# munia-ngc.net
KiCad netlist of a schematic drawn in EAGLE
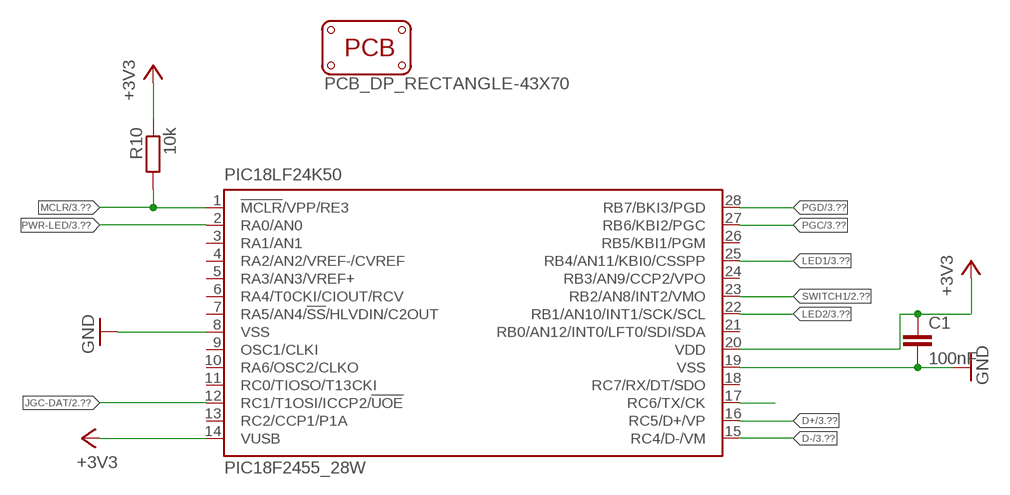
[diagram p0: schematic, sheet 1]
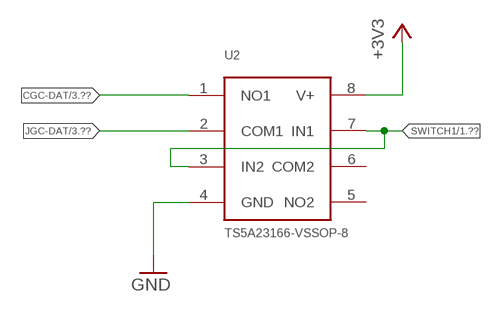
[diagram p1: schematic, sheet 2]
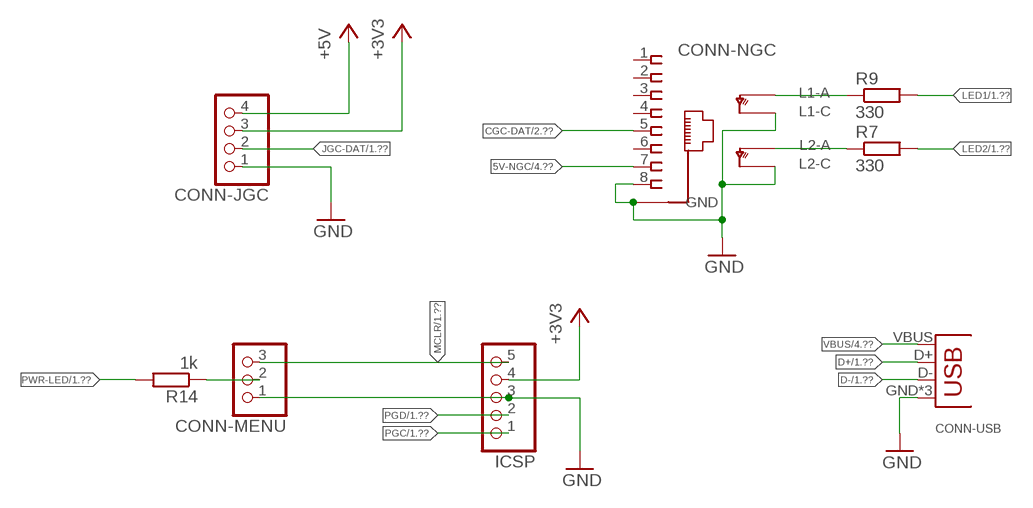
[diagram p2: schematic, sheet 3]
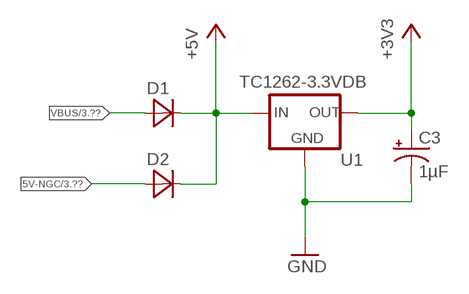
[diagram p3: schematic, sheet 4]

(export (version "E")
  (design (tool "Eeschema 10.0.6"))
  (components
    (comp (ref "C1")
      (value "100nF")
      (footprint "eagle-import:C0603")
      (libsource (lib "eagle-import") (part "C-EUC0603"))
    )
    (comp (ref "PCB1")
      (value "PCB_DP_RECTANGLE-43X70")
      (footprint "eagle-import:DP7043_V1")
      (libsource (lib "eagle-import") (part "PCB_DP_RECTANGLE-43X70"))
    )
    (comp (ref "PIC18LF24K50")
      (value "PIC18F2455_28W")
      (footprint "eagle-import:SO28W")
      (fields (field (name "MF") "MICROCHIP") (field (name "MPN") "PIC18F2455-I/SO"))
      (libsource (lib "eagle-import") (part "PIC18F2_28W455"))
    )
    (comp (ref "R10")
      (value "10k")
      (footprint "eagle-import:R0603")
      (libsource (lib "eagle-import") (part "R-EU_R0603"))
    )
    (comp (ref "C3")
      (value "1µF")
      (footprint "eagle-import:EIA3216")
      (libsource (lib "eagle-import") (part "TANT-CAP1206"))
    )
    (comp (ref "D1")
      (value "MBR120VLSFT1G")
      (footprint "eagle-import:SOD123")
      (libsource (lib "eagle-import") (part "MBR120VLSFT1G"))
    )
    (comp (ref "D2")
      (value "MBR120VLSFT1G")
      (footprint "eagle-import:SOD123")
      (libsource (lib "eagle-import") (part "MBR120VLSFT1G"))
    )
    (comp (ref "U1")
      (value "TC1262-3.3VDB")
      (footprint "eagle-import:SOT230P700X180-4N")
      (libsource (lib "eagle-import") (part "TC1262-3.3VDB"))
    )
    (comp (ref "U2")
      (value "TS5A23166-VSSOP-8")
      (footprint "eagle-import:SOT765")
      (libsource (lib "eagle-import") (part "TS5A23166-VSSOP-8"))
    )
    (comp (ref "CONN-JGC")
      (value "PINHD-1X4")
      (footprint "eagle-import:1X04")
      (libsource (lib "eagle-import") (part "PINHD-1X4"))
    )
    (comp (ref "CONN-MENU")
      (value "PINHD-1X3")
      (footprint "eagle-import:1X03")
      (libsource (lib "eagle-import") (part "PINHD-1X3"))
    )
    (comp (ref "CONN-NGC")
      (value "RJ45-NIELS")
      (footprint "eagle-import:RJ45-NIELS")
      (libsource (lib "eagle-import") (part "RJ45-NIELS"))
    )
    (comp (ref "CONN-USB")
      (value "USB-B-NIELS")
      (footprint "eagle-import:USB-B-H")
      (libsource (lib "eagle-import") (part "USB-B-NIELS"))
    )
    (comp (ref "ICSP")
      (value "PINHD-1X5")
      (footprint "eagle-import:1X05")
      (libsource (lib "eagle-import") (part "PINHD-1X5"))
    )
    (comp (ref "R7")
      (value "330")
      (footprint "eagle-import:R0603")
      (libsource (lib "eagle-import") (part "R-EU_R0603"))
    )
    (comp (ref "R9")
      (value "330")
      (footprint "eagle-import:R0603")
      (libsource (lib "eagle-import") (part "R-EU_R0603"))
    )
    (comp (ref "R14")
      (value "1k")
      (footprint "eagle-import:R0603")
      (libsource (lib "eagle-import") (part "R-EU_R0603"))
    )
  )
  (nets
    (net (code "1") (name "+3V3") (class "Default")
      (node (ref "C1") (pin "1") (pinfunction "1_1") (pintype "passive"))
      (node (ref "C3") (pin "A") (pinfunction "+_A") (pintype "passive"))
      (node (ref "CONN-JGC") (pin "3") (pinfunction "3_3") (pintype "passive"))
      (node (ref "ICSP") (pin "4") (pinfunction "4_4") (pintype "passive"))
      (node (ref "PIC18LF24K50") (pin "14") (pinfunction "VUSB_14") (pintype "bidirectional"))
      (node (ref "PIC18LF24K50") (pin "20") (pinfunction "VDD_20") (pintype "power_in"))
      (node (ref "R10") (pin "1") (pinfunction "1_1") (pintype "passive"))
      (node (ref "U1") (pin "3") (pinfunction "OUT_3") (pintype "passive"))
      (node (ref "U2") (pin "8") (pinfunction "V+_8") (pintype "bidirectional"))
    )
    (net (code "2") (name "+5V") (class "Default")
      (node (ref "CONN-JGC") (pin "4") (pinfunction "4_4") (pintype "passive"))
      (node (ref "D1") (pin "1") (pinfunction "C_1") (pintype "passive"))
      (node (ref "D2") (pin "1") (pinfunction "C_1") (pintype "passive"))
      (node (ref "U1") (pin "1") (pinfunction "IN_1") (pintype "input"))
    )
    (net (code "3") (name "5V-NGC") (class "Default")
      (node (ref "CONN-NGC") (pin "7") (pinfunction "7_7") (pintype "passive"))
      (node (ref "D2") (pin "2") (pinfunction "A_2") (pintype "passive"))
    )
    (net (code "4") (name "CGC-DAT") (class "Default")
      (node (ref "CONN-NGC") (pin "5") (pinfunction "5_5") (pintype "passive"))
      (node (ref "U2") (pin "1") (pinfunction "NO1_1") (pintype "bidirectional"))
    )
    (net (code "5") (name "D+") (class "Default")
      (node (ref "CONN-USB") (pin "D+") (pinfunction "D+_D+") (pintype "bidirectional"))
      (node (ref "PIC18LF24K50") (pin "16") (pinfunction "RC5/D+/VP_16") (pintype "bidirectional"))
    )
    (net (code "6") (name "D-") (class "Default")
      (node (ref "CONN-USB") (pin "D-") (pinfunction "D-_D-") (pintype "bidirectional"))
      (node (ref "PIC18LF24K50") (pin "15") (pinfunction "RC4/D-/VM_15") (pintype "bidirectional"))
    )
    (net (code "7") (name "GND") (class "Default")
      (node (ref "C1") (pin "2") (pinfunction "2_2") (pintype "passive"))
      (node (ref "C3") (pin "C") (pinfunction "-_C") (pintype "passive"))
      (node (ref "CONN-JGC") (pin "1") (pinfunction "1_1") (pintype "passive"))
      (node (ref "CONN-MENU") (pin "1") (pinfunction "1_1") (pintype "passive"))
      (node (ref "CONN-NGC") (pin "8") (pinfunction "8_8") (pintype "passive"))
      (node (ref "CONN-NGC") (pin "GND@5") (pinfunction "GND_GND@5") (pintype "power_in"))
      (node (ref "CONN-NGC") (pin "GND@6") (pinfunction "GND_GND@6") (pintype "power_in"))
      (node (ref "CONN-NGC") (pin "LED-GREEN-C") (pinfunction "L2C_LED-GREEN-C") (pintype "bidirectional"))
      (node (ref "CONN-NGC") (pin "LED-ORANGE-C") (pinfunction "L1C_LED-ORANGE-C") (pintype "bidirectional"))
      (node (ref "CONN-USB") (pin "GND") (pinfunction "GND_GND") (pintype "bidirectional"))
      (node (ref "CONN-USB") (pin "GND@1") (pinfunction "GND_GND@1") (pintype "bidirectional"))
      (node (ref "CONN-USB") (pin "GND@2") (pinfunction "GND_GND@2") (pintype "bidirectional"))
      (node (ref "ICSP") (pin "3") (pinfunction "3_3") (pintype "passive"))
      (node (ref "PIC18LF24K50") (pin "19") (pinfunction "VSS_19") (pintype "power_in"))
      (node (ref "PIC18LF24K50") (pin "8") (pinfunction "VSS_8") (pintype "power_in"))
      (node (ref "U1") (pin "2") (pinfunction "GND_2") (pintype "input"))
      (node (ref "U1") (pin "4") (pinfunction "GND_4") (pintype "input"))
      (node (ref "U2") (pin "4") (pinfunction "GND_4") (pintype "bidirectional"))
    )
    (net (code "8") (name "JGC-DAT") (class "Default")
      (node (ref "CONN-JGC") (pin "2") (pinfunction "2_2") (pintype "passive"))
      (node (ref "PIC18LF24K50") (pin "12") (pinfunction "RC1/T1OSI/ICCP2/~{UOE}_12") (pintype "bidirectional"))
      (node (ref "U2") (pin "2") (pinfunction "COM1_2") (pintype "bidirectional"))
    )
    (net (code "9") (name "LED1") (class "Default")
      (node (ref "PIC18LF24K50") (pin "25") (pinfunction "RB4/AN11/KBI0/CSSPP_25") (pintype "bidirectional"))
      (node (ref "R9") (pin "2") (pinfunction "2_2") (pintype "passive"))
    )
    (net (code "10") (name "LED2") (class "Default")
      (node (ref "PIC18LF24K50") (pin "22") (pinfunction "RB1/AN10/INT1/SCK/SCL_22") (pintype "bidirectional"))
      (node (ref "R7") (pin "2") (pinfunction "2_2") (pintype "passive"))
    )
    (net (code "11") (name "MCLR") (class "Default")
      (node (ref "CONN-MENU") (pin "3") (pinfunction "3_3") (pintype "passive"))
      (node (ref "ICSP") (pin "5") (pinfunction "5_5") (pintype "passive"))
      (node (ref "PIC18LF24K50") (pin "1") (pinfunction "~{MCLR}/VPP/RE3_1") (pintype "input"))
      (node (ref "R10") (pin "2") (pinfunction "2_2") (pintype "passive"))
    )
    (net (code "12") (name "Net-(CONN-MENU-Pad2)") (class "Default")
      (node (ref "CONN-MENU") (pin "2") (pinfunction "2_2") (pintype "passive"))
      (node (ref "R14") (pin "1") (pinfunction "1_1") (pintype "passive"))
    )
    (net (code "13") (name "Net-(CONN-NGC-L1A)") (class "Default")
      (node (ref "CONN-NGC") (pin "LED-ORANGE-A") (pinfunction "L1A_LED-ORANGE-A") (pintype "bidirectional"))
      (node (ref "R9") (pin "1") (pinfunction "1_1") (pintype "passive"))
    )
    (net (code "14") (name "Net-(CONN-NGC-L2A)") (class "Default")
      (node (ref "CONN-NGC") (pin "LED-GREEN-A") (pinfunction "L2A_LED-GREEN-A") (pintype "bidirectional"))
      (node (ref "R7") (pin "1") (pinfunction "1_1") (pintype "passive"))
    )
    (net (code "15") (name "PGC") (class "Default")
      (node (ref "ICSP") (pin "1") (pinfunction "1_1") (pintype "passive"))
      (node (ref "PIC18LF24K50") (pin "27") (pinfunction "RB6/KBI2/PGC_27") (pintype "bidirectional"))
    )
    (net (code "16") (name "PGD") (class "Default")
      (node (ref "ICSP") (pin "2") (pinfunction "2_2") (pintype "passive"))
      (node (ref "PIC18LF24K50") (pin "28") (pinfunction "RB7/BKI3/PGD_28") (pintype "bidirectional"))
    )
    (net (code "17") (name "PWR-LED") (class "Default")
      (node (ref "PIC18LF24K50") (pin "2") (pinfunction "RA0/AN0_2") (pintype "bidirectional"))
      (node (ref "R14") (pin "2") (pinfunction "2_2") (pintype "passive"))
    )
    (net (code "18") (name "SWITCH1") (class "Default")
      (node (ref "PIC18LF24K50") (pin "23") (pinfunction "RB2/AN8/INT2/VMO_23") (pintype "bidirectional"))
      (node (ref "U2") (pin "3") (pinfunction "IN2_3") (pintype "bidirectional"))
      (node (ref "U2") (pin "7") (pinfunction "IN1_7") (pintype "bidirectional"))
    )
    (net (code "19") (name "VBUS") (class "Default")
      (node (ref "CONN-USB") (pin "VBUS") (pinfunction "VBUS_VBUS") (pintype "bidirectional"))
      (node (ref "D1") (pin "2") (pinfunction "A_2") (pintype "passive"))
    )
    (net (code "20") (name "unconnected-(CONN-NGC-Pad1)") (class "Default")
      (node (ref "CONN-NGC") (pin "1") (pinfunction "1_1") (pintype "passive"))
    )
    (net (code "21") (name "unconnected-(CONN-NGC-Pad2)") (class "Default")
      (node (ref "CONN-NGC") (pin "2") (pinfunction "2_2") (pintype "passive"))
    )
    (net (code "22") (name "unconnected-(CONN-NGC-Pad3)") (class "Default")
      (node (ref "CONN-NGC") (pin "3") (pinfunction "3_3") (pintype "passive"))
    )
    (net (code "23") (name "unconnected-(CONN-NGC-Pad4)") (class "Default")
      (node (ref "CONN-NGC") (pin "4") (pinfunction "4_4") (pintype "passive"))
    )
    (net (code "24") (name "unconnected-(CONN-NGC-Pad6)") (class "Default")
      (node (ref "CONN-NGC") (pin "6") (pinfunction "6_6") (pintype "passive"))
    )
    (net (code "25") (name "unconnected-(PIC18LF24K50-OSC1{slash}CLKI-Pad9)") (class "Default")
      (node (ref "PIC18LF24K50") (pin "9") (pinfunction "OSC1/CLKI_9") (pintype "input"))
    )
    (net (code "26") (name "unconnected-(PIC18LF24K50-RA1{slash}AN1-Pad3)") (class "Default")
      (node (ref "PIC18LF24K50") (pin "3") (pinfunction "RA1/AN1_3") (pintype "bidirectional"))
    )
    (net (code "27") (name "unconnected-(PIC18LF24K50-RA2{slash}AN2{slash}VREF-{slash}CVREF-Pad4)") (class "Default")
      (node (ref "PIC18LF24K50") (pin "4") (pinfunction "RA2/AN2/VREF-/CVREF_4") (pintype "bidirectional"))
    )
    (net (code "28") (name "unconnected-(PIC18LF24K50-RA3{slash}AN3{slash}VREF+-Pad5)") (class "Default")
      (node (ref "PIC18LF24K50") (pin "5") (pinfunction "RA3/AN3/VREF+_5") (pintype "bidirectional"))
    )
    (net (code "29") (name "unconnected-(PIC18LF24K50-RA4{slash}T0CKI{slash}CIOUT{slash}RCV-Pad6)") (class "Default")
      (node (ref "PIC18LF24K50") (pin "6") (pinfunction "RA4/T0CKI/CIOUT/RCV_6") (pintype "bidirectional"))
    )
    (net (code "30") (name "unconnected-(PIC18LF24K50-RA5{slash}AN4{slash}~{SS}{slash}HLVDIN{slash}C2OUT-Pad7)") (class "Default")
      (node (ref "PIC18LF24K50") (pin "7") (pinfunction "RA5/AN4/~{SS}/HLVDIN/C2OUT_7") (pintype "bidirectional"))
    )
    (net (code "31") (name "unconnected-(PIC18LF24K50-RA6{slash}OSC2{slash}CLKO-Pad10)") (class "Default")
      (node (ref "PIC18LF24K50") (pin "10") (pinfunction "RA6/OSC2/CLKO_10") (pintype "output"))
    )
    (net (code "32") (name "unconnected-(PIC18LF24K50-RB0{slash}AN12{slash}INT0{slash}LFT0{slash}SDI{slash}SDA-Pad21)") (class "Default")
      (node (ref "PIC18LF24K50") (pin "21") (pinfunction "RB0/AN12/INT0/LFT0/SDI/SDA_21") (pintype "bidirectional"))
    )
    (net (code "33") (name "unconnected-(PIC18LF24K50-RB3{slash}AN9{slash}CCP2{slash}VPO-Pad24)") (class "Default")
      (node (ref "PIC18LF24K50") (pin "24") (pinfunction "RB3/AN9/CCP2/VPO_24") (pintype "bidirectional"))
    )
    (net (code "34") (name "unconnected-(PIC18LF24K50-RB5{slash}KBI1{slash}PGM-Pad26)") (class "Default")
      (node (ref "PIC18LF24K50") (pin "26") (pinfunction "RB5/KBI1/PGM_26") (pintype "bidirectional"))
    )
    (net (code "35") (name "unconnected-(PIC18LF24K50-RC0{slash}TIOSO{slash}T13CKI-Pad11)") (class "Default")
      (node (ref "PIC18LF24K50") (pin "11") (pinfunction "RC0/TIOSO/T13CKI_11") (pintype "bidirectional"))
    )
    (net (code "36") (name "unconnected-(PIC18LF24K50-RC2{slash}CCP1{slash}P1A-Pad13)") (class "Default")
      (node (ref "PIC18LF24K50") (pin "13") (pinfunction "RC2/CCP1/P1A_13") (pintype "bidirectional"))
    )
    (net (code "37") (name "unconnected-(PIC18LF24K50-RC6{slash}TX{slash}CK-Pad17)") (class "Default")
      (node (ref "PIC18LF24K50") (pin "17") (pinfunction "RC6/TX/CK_17") (pintype "bidirectional"))
    )
    (net (code "38") (name "unconnected-(PIC18LF24K50-RC7{slash}RX{slash}DT{slash}SDO-Pad18)") (class "Default")
      (node (ref "PIC18LF24K50") (pin "18") (pinfunction "RC7/RX/DT/SDO_18") (pintype "bidirectional"))
    )
    (net (code "39") (name "unconnected-(U2-COM2-Pad6)") (class "Default")
      (node (ref "U2") (pin "6") (pinfunction "COM2_6") (pintype "bidirectional"))
    )
    (net (code "40") (name "unconnected-(U2-NO2-Pad5)") (class "Default")
      (node (ref "U2") (pin "5") (pinfunction "NO2_5") (pintype "bidirectional"))
    )
  )
)
